# smart_oven.net
KiCad netlist of a schematic drawn in Altium Designer
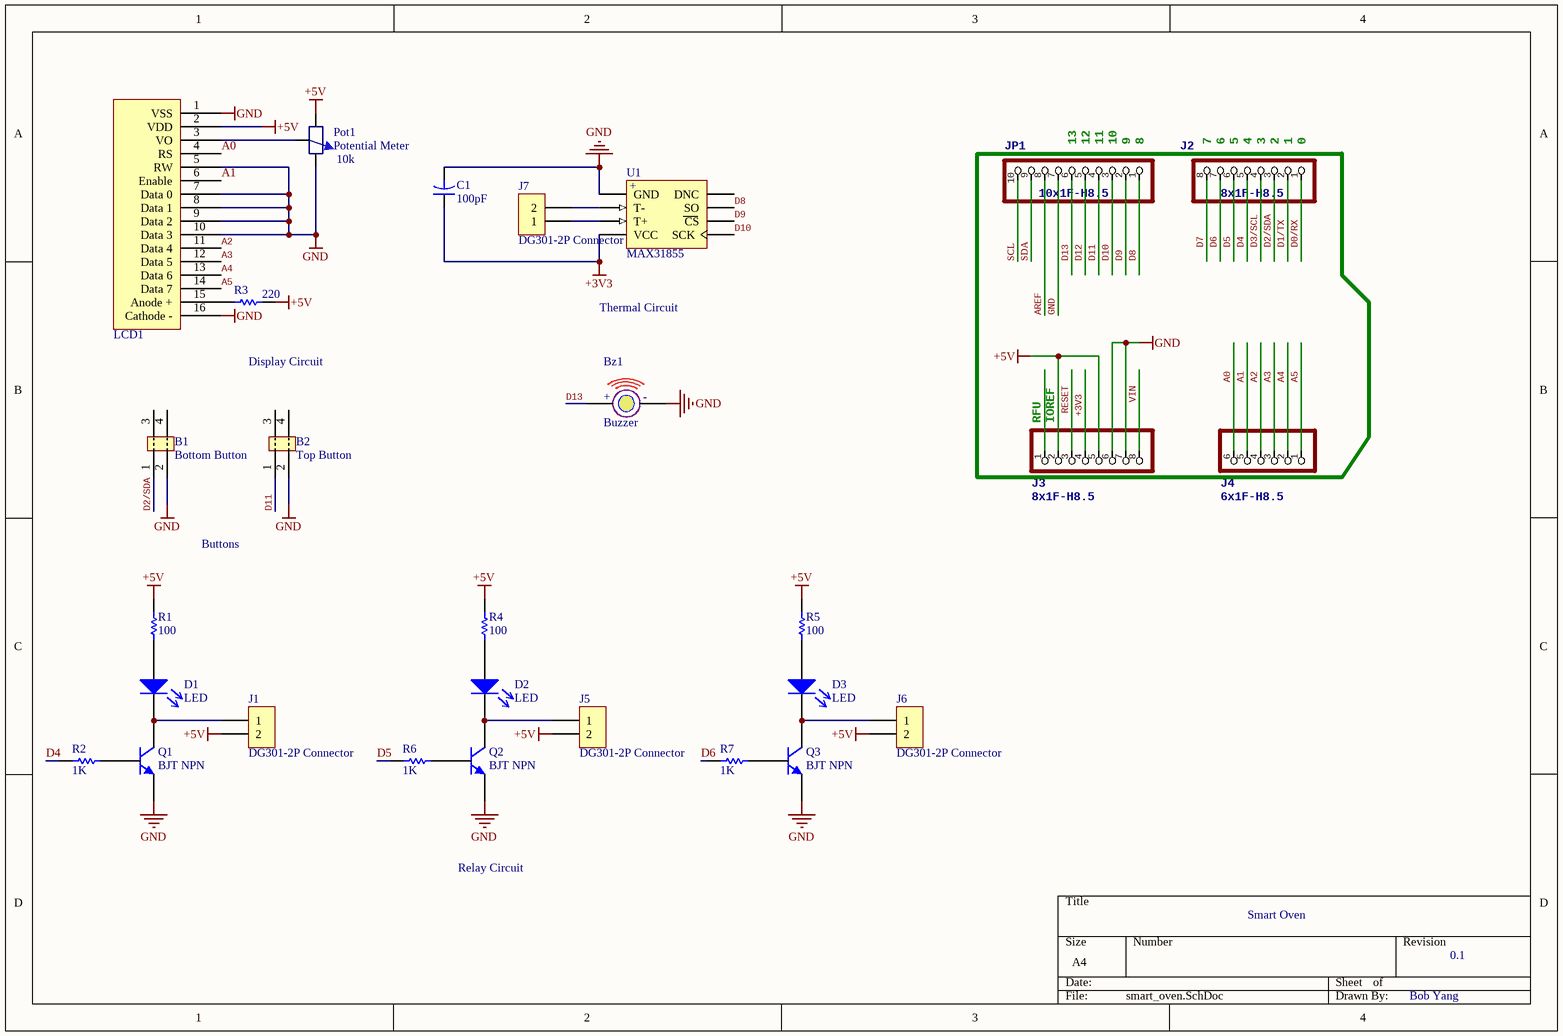
[diagram p0: smart_oven.SchDoc]

(export (version "E")
  (design (tool "Eeschema 10.0.6"))
  (components
    (comp (ref "B1")
      (value "Bottom Button")
      (footprint "push button")
      (description "Push Button")
      (libsource (lib "my-common") (part "Push Button"))
    )
    (comp (ref "B2")
      (value "Top Button")
      (footprint "push button")
      (description "Push Button")
      (libsource (lib "my-common") (part "Push Button"))
    )
    (comp (ref "Bz1")
      (value "Buzzer")
      (footprint "Buzzer")
      (description "Piezo Buzzer")
      (libsource (lib "my-common") (part "Buzzer"))
    )
    (comp (ref "C1")
      (value "100pF")
      (footprint "CAPR5-4X5")
      (description "Capacitor")
      (fields (field (name "Comment") "Cap2") (field (name "PUBLISHER") "Altium Limited"))
      (libsource (lib "Miscellaneous Devices") (part "Cap2"))
    )
    (comp (ref "D1") (value "LED") (footprint "LED TOP92") (libsource (lib "my-common") (part "LED")))
    (comp (ref "D2") (value "LED") (footprint "LED TOP92") (libsource (lib "my-common") (part "LED")))
    (comp (ref "D3") (value "LED") (footprint "LED TOP92") (libsource (lib "my-common") (part "LED")))
    (comp (ref "J1")
      (value "DG301-2P Connector")
      (footprint "DG301-2P Connector")
      (libsource (lib "my-common") (part "DG301-2P Connector"))
    )
    (comp (ref "J2")
      (value "8x1F-H8.5")
      (footprint "PINHD-1X8")
      (description "PIN HEADER")
      (libsource (lib "SmartPrj") (part "PINHD-1X8"))
    )
    (comp (ref "J3")
      (value "8x1F-H8.5")
      (footprint "PINHD-1X8")
      (description "PIN HEADER")
      (libsource (lib "SmartPrj") (part "PINHD-1X8"))
    )
    (comp (ref "J4")
      (value "6x1F-H8.5")
      (footprint "PINHD-1X6")
      (description "PIN HEADER")
      (libsource (lib "SmartPrj") (part "PINHD-1X6"))
    )
    (comp (ref "J5")
      (value "DG301-2P Connector")
      (footprint "DG301-2P Connector")
      (libsource (lib "my-common") (part "DG301-2P Connector"))
    )
    (comp (ref "J6")
      (value "DG301-2P Connector")
      (footprint "DG301-2P Connector")
      (libsource (lib "my-common") (part "DG301-2P Connector"))
    )
    (comp (ref "J7")
      (value "DG301-2P Connector")
      (footprint "DG301-2P Connector")
      (libsource (lib "") (part "DG301-2P Connector_1"))
    )
    (comp (ref "JP1")
      (value "10x1F-H8.5")
      (footprint "PINHD-1X10")
      (description "PIN HEADER")
      (libsource (lib "SmartPrj") (part "PINHD-1X10"))
    )
    (comp (ref "LCD1")
      (value "LCD1602")
      (footprint "LCD1602")
      (description "LCD 1602")
      (libsource (lib "my-common") (part "LCD1602"))
    )
    (comp (ref "Pot1")
      (value "Potential Meter")
      (footprint "Axial ThrimPot")
      (fields (field (name "ALTIUM_VALUE") "10k"))
      (libsource (lib "my-common") (part "Potential Meter"))
    )
    (comp (ref "Q1") (value "BJT NPN") (footprint "BJT TOP92") (libsource (lib "my-common") (part "BJT NPN")))
    (comp (ref "Q2") (value "BJT NPN") (footprint "BJT TOP92") (libsource (lib "my-common") (part "BJT NPN")))
    (comp (ref "Q3") (value "BJT NPN") (footprint "BJT TOP92") (libsource (lib "my-common") (part "BJT NPN")))
    (comp (ref "R1")
      (value "100")
      (footprint "AXIAL-0.3")
      (description "Resistor")
      (fields (field (name "Comment") "Res1") (field (name "PUBLISHER") "Altium Limited"))
      (libsource (lib "Miscellaneous Devices") (part "Res1"))
    )
    (comp (ref "R2")
      (value "1K")
      (footprint "AXIAL-0.3")
      (description "Resistor")
      (fields (field (name "Comment") "Res1") (field (name "PUBLISHER") "Altium Limited"))
      (libsource (lib "Miscellaneous Devices") (part "Res1"))
    )
    (comp (ref "R3")
      (value "220")
      (footprint "AXIAL-0.3")
      (description "Resistor")
      (fields (field (name "Comment") "Res1") (field (name "PUBLISHER") "Altium Limited"))
      (libsource (lib "Miscellaneous Devices") (part "Res1"))
    )
    (comp (ref "R4")
      (value "100")
      (footprint "AXIAL-0.3")
      (description "Resistor")
      (fields (field (name "Comment") "Res1") (field (name "PUBLISHER") "Altium Limited"))
      (libsource (lib "Miscellaneous Devices") (part "Res1"))
    )
    (comp (ref "R5")
      (value "100")
      (footprint "AXIAL-0.3")
      (description "Resistor")
      (fields (field (name "Comment") "Res1") (field (name "PUBLISHER") "Altium Limited"))
      (libsource (lib "Miscellaneous Devices") (part "Res1"))
    )
    (comp (ref "R6")
      (value "1K")
      (footprint "AXIAL-0.3")
      (description "Resistor")
      (fields (field (name "Comment") "Res1") (field (name "PUBLISHER") "Altium Limited"))
      (libsource (lib "Miscellaneous Devices") (part "Res1"))
    )
    (comp (ref "R7")
      (value "1K")
      (footprint "AXIAL-0.3")
      (description "Resistor")
      (fields (field (name "Comment") "Res1") (field (name "PUBLISHER") "Altium Limited"))
      (libsource (lib "Miscellaneous Devices") (part "Res1"))
    )
    (comp (ref "U1")
      (value "MAX31855")
      (footprint "SOP8 Breakout")
      (description "K thermal-couple reading IC")
      (libsource (lib "my-common") (part "MAX31855"))
    )
  )
  (nets
    (net (code "1") (name "+3V3") (class "Default")
      (node (ref "C1") (pin "1") (pinfunction "1_1") (pintype "passive"))
      (node (ref "J3") (pin "4") (pinfunction "4_4") (pintype "passive"))
      (node (ref "U1") (pin "4") (pinfunction "VCC_4") (pintype "power_in"))
    )
    (net (code "2") (name "+5V") (class "Default")
      (node (ref "J1") (pin "2") (pinfunction "2_2") (pintype "passive"))
      (node (ref "J3") (pin "2") (pinfunction "2_2") (pintype "passive"))
      (node (ref "J3") (pin "5") (pinfunction "5_5") (pintype "passive"))
      (node (ref "J5") (pin "2") (pinfunction "2_2") (pintype "passive"))
      (node (ref "J6") (pin "2") (pinfunction "2_2") (pintype "passive"))
      (node (ref "LCD1") (pin "2") (pinfunction "VDD_2") (pintype "power_in"))
      (node (ref "Pot1") (pin "1") (pintype "passive"))
      (node (ref "R1") (pin "2") (pinfunction "2_2") (pintype "passive"))
      (node (ref "R3") (pin "2") (pinfunction "2_2") (pintype "passive"))
      (node (ref "R4") (pin "2") (pinfunction "2_2") (pintype "passive"))
      (node (ref "R5") (pin "2") (pinfunction "2_2") (pintype "passive"))
    )
    (net (code "3") (name "/A0") (class "Default")
      (node (ref "J4") (pin "6") (pinfunction "6_6") (pintype "passive"))
      (node (ref "LCD1") (pin "4") (pinfunction "RS_4") (pintype "passive"))
    )
    (net (code "4") (name "/A1") (class "Default")
      (node (ref "J4") (pin "5") (pinfunction "5_5") (pintype "passive"))
      (node (ref "LCD1") (pin "6") (pinfunction "Enable_6") (pintype "passive"))
    )
    (net (code "5") (name "/A2") (class "Default")
      (node (ref "J4") (pin "4") (pinfunction "4_4") (pintype "passive"))
      (node (ref "LCD1") (pin "11") (pinfunction "Data_4_11") (pintype "passive"))
    )
    (net (code "6") (name "/A3") (class "Default")
      (node (ref "J4") (pin "3") (pinfunction "3_3") (pintype "passive"))
      (node (ref "LCD1") (pin "12") (pinfunction "Data_5_12") (pintype "passive"))
    )
    (net (code "7") (name "/A4") (class "Default")
      (node (ref "J4") (pin "2") (pinfunction "2_2") (pintype "passive"))
      (node (ref "LCD1") (pin "13") (pinfunction "Data_6_13") (pintype "passive"))
    )
    (net (code "8") (name "/A5") (class "Default")
      (node (ref "J4") (pin "1") (pinfunction "1_1") (pintype "passive"))
      (node (ref "LCD1") (pin "14") (pinfunction "Data_7_14") (pintype "passive"))
    )
    (net (code "9") (name "/AREF") (class "Default")
      (node (ref "JP1") (pin "8") (pinfunction "8_8") (pintype "passive"))
    )
    (net (code "10") (name "/D0{slash}RX") (class "Default")
      (node (ref "J2") (pin "1") (pinfunction "1_1") (pintype "passive"))
    )
    (net (code "11") (name "/D1{slash}TX") (class "Default")
      (node (ref "J2") (pin "2") (pinfunction "2_2") (pintype "passive"))
    )
    (net (code "12") (name "/D2{slash}SDA") (class "Default")
      (node (ref "B1") (pin "1") (pinfunction "1_1") (pintype "passive"))
      (node (ref "J2") (pin "3") (pinfunction "3_3") (pintype "passive"))
    )
    (net (code "13") (name "/D3{slash}SCL") (class "Default")
      (node (ref "J2") (pin "4") (pinfunction "4_4") (pintype "passive"))
    )
    (net (code "14") (name "/D4") (class "Default")
      (node (ref "J2") (pin "5") (pinfunction "5_5") (pintype "passive"))
      (node (ref "R2") (pin "2") (pinfunction "2_2") (pintype "passive"))
    )
    (net (code "15") (name "/D5") (class "Default")
      (node (ref "J2") (pin "6") (pinfunction "6_6") (pintype "passive"))
      (node (ref "R6") (pin "2") (pinfunction "2_2") (pintype "passive"))
    )
    (net (code "16") (name "/D6") (class "Default")
      (node (ref "J2") (pin "7") (pinfunction "7_7") (pintype "passive"))
      (node (ref "R7") (pin "2") (pinfunction "2_2") (pintype "passive"))
    )
    (net (code "17") (name "/D7") (class "Default")
      (node (ref "J2") (pin "8") (pinfunction "8_8") (pintype "passive"))
    )
    (net (code "18") (name "/D8") (class "Default")
      (node (ref "JP1") (pin "1") (pinfunction "1_1") (pintype "passive"))
      (node (ref "U1") (pin "7") (pinfunction "SO_7") (pintype "passive"))
    )
    (net (code "19") (name "/D9") (class "Default")
      (node (ref "JP1") (pin "2") (pinfunction "2_2") (pintype "passive"))
      (node (ref "U1") (pin "6") (pinfunction "CS_6") (pintype "passive"))
    )
    (net (code "20") (name "/D10") (class "Default")
      (node (ref "JP1") (pin "3") (pinfunction "3_3") (pintype "passive"))
      (node (ref "U1") (pin "5") (pinfunction "SCK_5") (pintype "power_in"))
    )
    (net (code "21") (name "/D11") (class "Default")
      (node (ref "B2") (pin "1") (pinfunction "1_1") (pintype "passive"))
      (node (ref "JP1") (pin "4") (pinfunction "4_4") (pintype "passive"))
    )
    (net (code "22") (name "/D12") (class "Default")
      (node (ref "JP1") (pin "5") (pinfunction "5_5") (pintype "passive"))
    )
    (net (code "23") (name "/D13") (class "Default")
      (node (ref "Bz1") (pin "1") (pinfunction "+_1") (pintype "passive"))
      (node (ref "JP1") (pin "6") (pinfunction "6_6") (pintype "passive"))
    )
    (net (code "24") (name "/RESET") (class "Default")
      (node (ref "J3") (pin "3") (pinfunction "3_3") (pintype "passive"))
    )
    (net (code "25") (name "/SCL") (class "Default")
      (node (ref "JP1") (pin "10") (pinfunction "10_10") (pintype "passive"))
    )
    (net (code "26") (name "/SDA") (class "Default")
      (node (ref "JP1") (pin "9") (pinfunction "9_9") (pintype "passive"))
    )
    (net (code "27") (name "/VIN") (class "Default")
      (node (ref "J3") (pin "8") (pinfunction "8_8") (pintype "passive"))
    )
    (net (code "28") (name "GND") (class "Default")
      (node (ref "B1") (pin "2") (pinfunction "2_2") (pintype "passive"))
      (node (ref "B2") (pin "2") (pinfunction "2_2") (pintype "passive"))
      (node (ref "Bz1") (pin "2") (pinfunction "-_2") (pintype "passive"))
      (node (ref "C1") (pin "2") (pinfunction "2_2") (pintype "passive"))
      (node (ref "J3") (pin "6") (pinfunction "6_6") (pintype "passive"))
      (node (ref "J3") (pin "7") (pinfunction "7_7") (pintype "passive"))
      (node (ref "JP1") (pin "7") (pinfunction "7_7") (pintype "passive"))
      (node (ref "LCD1") (pin "1") (pinfunction "VSS_1") (pintype "power_in"))
      (node (ref "LCD1") (pin "10") (pinfunction "Data_3_10") (pintype "passive"))
      (node (ref "LCD1") (pin "16") (pinfunction "Cathode_-_16") (pintype "power_in"))
      (node (ref "LCD1") (pin "5") (pinfunction "RW_5") (pintype "passive"))
      (node (ref "LCD1") (pin "7") (pinfunction "Data_0_7") (pintype "passive"))
      (node (ref "LCD1") (pin "8") (pinfunction "Data_1_8") (pintype "passive"))
      (node (ref "LCD1") (pin "9") (pinfunction "Data_2_9") (pintype "passive"))
      (node (ref "Pot1") (pin "2") (pintype "passive"))
      (node (ref "Q1") (pin "e") (pinfunction "e_e") (pintype "passive"))
      (node (ref "Q2") (pin "e") (pinfunction "e_e") (pintype "passive"))
      (node (ref "Q3") (pin "e") (pinfunction "e_e") (pintype "passive"))
      (node (ref "U1") (pin "1") (pinfunction "GND_1") (pintype "power_in"))
    )
    (net (code "29") (name "Net-(D1-Pad1)") (class "Default")
      (node (ref "D1") (pin "1") (pinfunction "1_1") (pintype "passive"))
      (node (ref "R1") (pin "1") (pinfunction "1_1") (pintype "passive"))
    )
    (net (code "30") (name "Net-(D1-Pad2)") (class "Default")
      (node (ref "D1") (pin "2") (pinfunction "2_2") (pintype "passive"))
      (node (ref "J1") (pin "1") (pinfunction "1_1") (pintype "passive"))
      (node (ref "Q1") (pin "c") (pinfunction "c_c") (pintype "passive"))
    )
    (net (code "31") (name "Net-(D2-Pad1)") (class "Default")
      (node (ref "D2") (pin "1") (pinfunction "1_1") (pintype "passive"))
      (node (ref "R4") (pin "1") (pinfunction "1_1") (pintype "passive"))
    )
    (net (code "32") (name "Net-(D2-Pad2)") (class "Default")
      (node (ref "D2") (pin "2") (pinfunction "2_2") (pintype "passive"))
      (node (ref "J5") (pin "1") (pinfunction "1_1") (pintype "passive"))
      (node (ref "Q2") (pin "c") (pinfunction "c_c") (pintype "passive"))
    )
    (net (code "33") (name "Net-(D3-Pad1)") (class "Default")
      (node (ref "D3") (pin "1") (pinfunction "1_1") (pintype "passive"))
      (node (ref "R5") (pin "1") (pinfunction "1_1") (pintype "passive"))
    )
    (net (code "34") (name "Net-(D3-Pad2)") (class "Default")
      (node (ref "D3") (pin "2") (pinfunction "2_2") (pintype "passive"))
      (node (ref "J6") (pin "1") (pinfunction "1_1") (pintype "passive"))
      (node (ref "Q3") (pin "c") (pinfunction "c_c") (pintype "passive"))
    )
    (net (code "35") (name "Net-(LCD1-Anode_+)") (class "Default")
      (node (ref "LCD1") (pin "15") (pinfunction "Anode_+_15") (pintype "power_in"))
      (node (ref "R3") (pin "1") (pinfunction "1_1") (pintype "passive"))
    )
    (net (code "36") (name "Net-(LCD1-VO)") (class "Default")
      (node (ref "LCD1") (pin "3") (pinfunction "VO_3") (pintype "passive"))
      (node (ref "Pot1") (pin "3") (pinfunction "3_3") (pintype "passive"))
    )
    (net (code "37") (name "Net-(Q1-Padb)") (class "Default")
      (node (ref "Q1") (pin "b") (pinfunction "b_b") (pintype "passive"))
      (node (ref "R2") (pin "1") (pinfunction "1_1") (pintype "passive"))
    )
    (net (code "38") (name "Net-(Q2-Padb)") (class "Default")
      (node (ref "Q2") (pin "b") (pinfunction "b_b") (pintype "passive"))
      (node (ref "R6") (pin "1") (pinfunction "1_1") (pintype "passive"))
    )
    (net (code "39") (name "Net-(Q3-Padb)") (class "Default")
      (node (ref "Q3") (pin "b") (pinfunction "b_b") (pintype "passive"))
      (node (ref "R7") (pin "1") (pinfunction "1_1") (pintype "passive"))
    )
    (net (code "40") (name "Net-(U1-T+)") (class "Default")
      (node (ref "J7") (pin "1") (pinfunction "1_1") (pintype "passive"))
      (node (ref "U1") (pin "3") (pinfunction "T+_3") (pintype "input"))
    )
    (net (code "41") (name "Net-(U1-T-)") (class "Default")
      (node (ref "J7") (pin "2") (pinfunction "2_2") (pintype "passive"))
      (node (ref "U1") (pin "2") (pinfunction "T-_2") (pintype "input"))
    )
    (net (code "42") (name "unconnected-(B1-Pad3)") (class "Default")
      (node (ref "B1") (pin "3") (pinfunction "3_3") (pintype "passive"))
    )
    (net (code "43") (name "unconnected-(B1-Pad4)") (class "Default")
      (node (ref "B1") (pin "4") (pinfunction "4_4") (pintype "passive"))
    )
    (net (code "44") (name "unconnected-(B2-Pad3)") (class "Default")
      (node (ref "B2") (pin "3") (pinfunction "3_3") (pintype "passive"))
    )
    (net (code "45") (name "unconnected-(B2-Pad4)") (class "Default")
      (node (ref "B2") (pin "4") (pinfunction "4_4") (pintype "passive"))
    )
    (net (code "46") (name "unconnected-(J3-Pad1)") (class "Default")
      (node (ref "J3") (pin "1") (pinfunction "1_1") (pintype "passive"))
    )
    (net (code "47") (name "unconnected-(U1-DNC-Pad8)") (class "Default")
      (node (ref "U1") (pin "8") (pinfunction "DNC_8") (pintype "passive"))
    )
  )
)
